# octopus_sch.net
KiCad netlist of a schematic drawn in Altium Designer
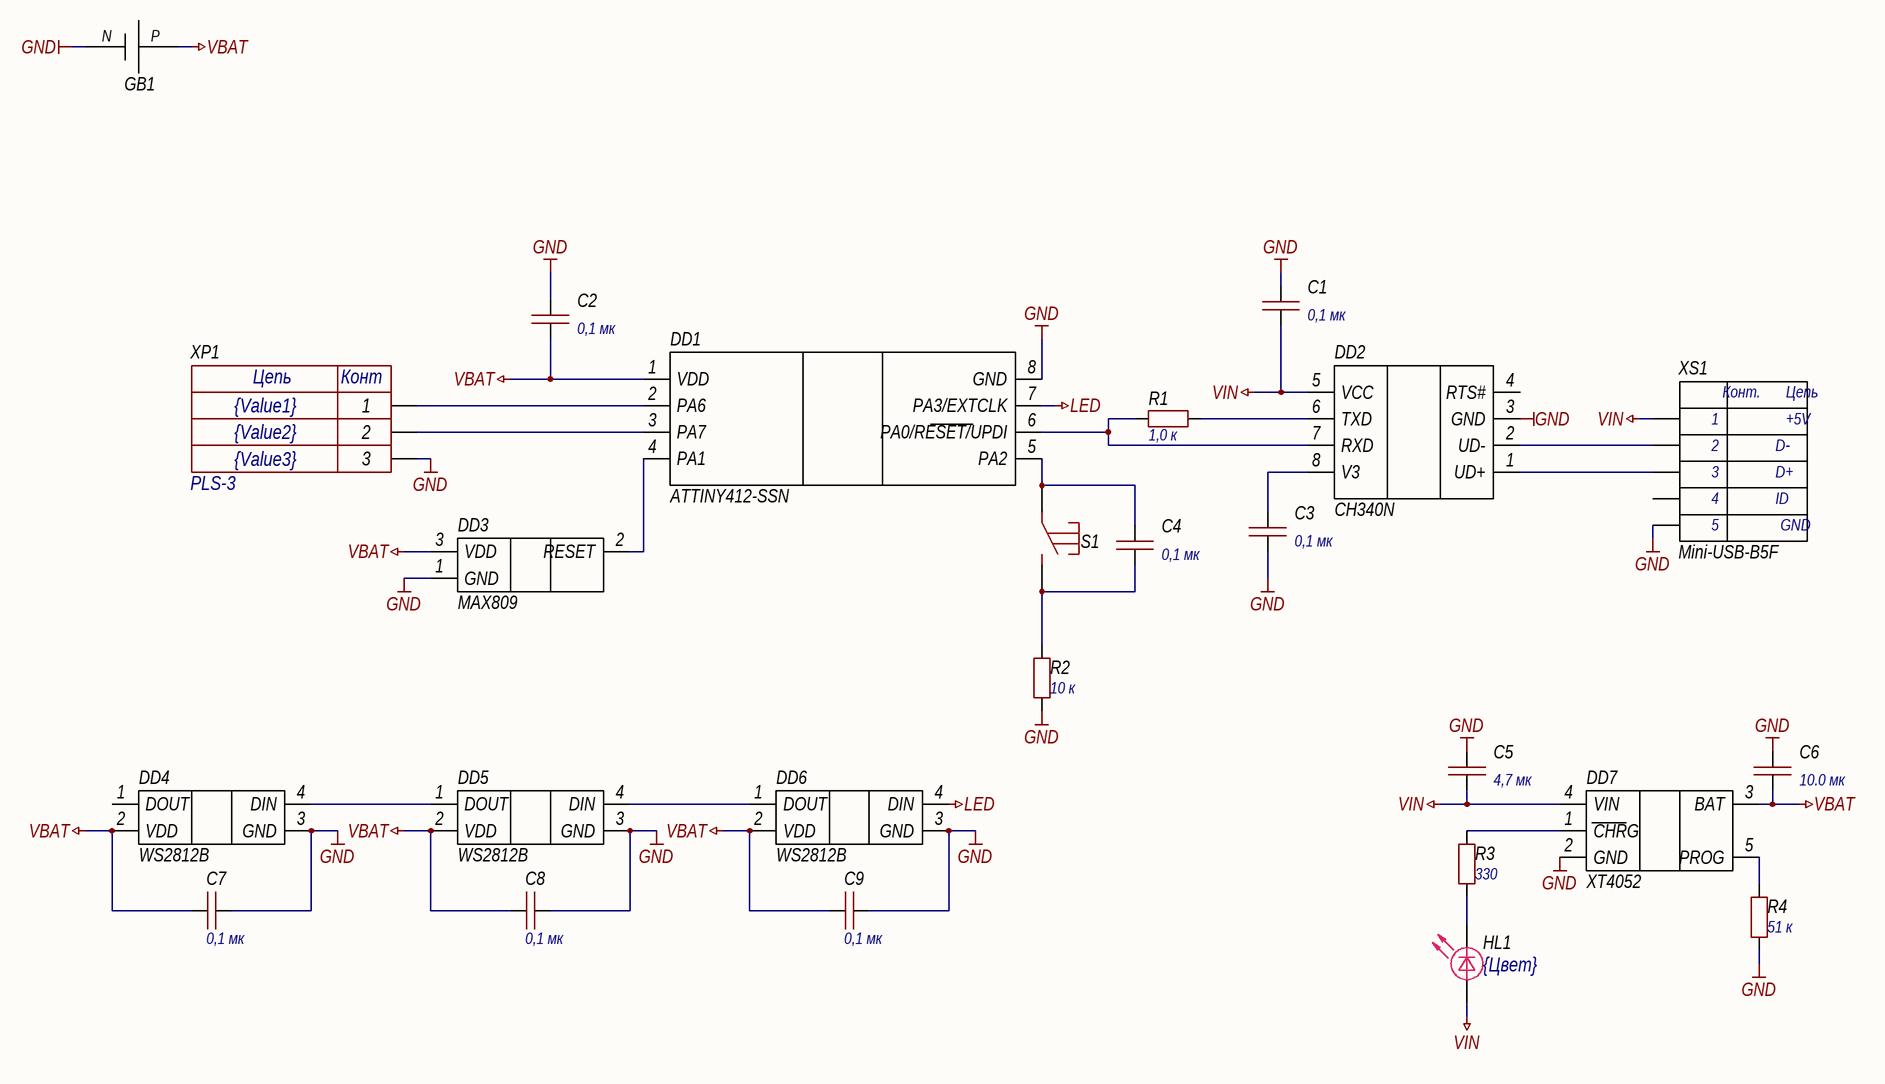
[diagram p0: octopus_sch.SchDoc]

(export (version "E")
  (design (tool "Eeschema 10.0.6"))
  (components
    (comp (ref "C1")
      (value "0,1 мк")
      (footprint "THT CAP")
      (description "Конденсатор")
      (fields (field (name "PART NUMBER") "Capacitor"))
      (libsource (lib "Hydrolib") (part "Capacitor"))
    )
    (comp (ref "C2")
      (value "0,1 мк")
      (footprint "THT CAP")
      (description "Конденсатор")
      (fields (field (name "PART NUMBER") "Capacitor"))
      (libsource (lib "Hydrolib") (part "Capacitor"))
    )
    (comp (ref "C3")
      (value "0,1 мк")
      (footprint "THT CAP")
      (description "Конденсатор")
      (fields (field (name "PART NUMBER") "Capacitor"))
      (libsource (lib "Hydrolib") (part "Capacitor"))
    )
    (comp (ref "C4")
      (value "0,1 мк")
      (footprint "THT CAP")
      (description "Конденсатор")
      (fields (field (name "PART NUMBER") "Capacitor"))
      (libsource (lib "Hydrolib") (part "Capacitor"))
    )
    (comp (ref "C5")
      (value "4,7 мк")
      (footprint "THT CAP")
      (description "Конденсатор")
      (fields (field (name "PART NUMBER") "Capacitor"))
      (libsource (lib "Hydrolib") (part "Capacitor"))
    )
    (comp (ref "C6")
      (value "10.0 мк")
      (footprint "THT CAP")
      (description "Конденсатор")
      (fields (field (name "PART NUMBER") "Capacitor"))
      (libsource (lib "Hydrolib") (part "Capacitor"))
    )
    (comp (ref "C7")
      (value "0,1 мк")
      (footprint "THT CAP")
      (description "Конденсатор")
      (fields (field (name "PART NUMBER") "Capacitor"))
      (libsource (lib "Hydrolib") (part "Capacitor"))
    )
    (comp (ref "C8")
      (value "0,1 мк")
      (footprint "THT CAP")
      (description "Конденсатор")
      (fields (field (name "PART NUMBER") "Capacitor"))
      (libsource (lib "Hydrolib") (part "Capacitor"))
    )
    (comp (ref "C9")
      (value "0,1 мк")
      (footprint "THT CAP")
      (description "Конденсатор")
      (fields (field (name "PART NUMBER") "Capacitor"))
      (libsource (lib "Hydrolib") (part "Capacitor"))
    )
    (comp (ref "DD1")
      (value "ATTINY412-SSN")
      (footprint "SOIC-8")
      (description "Микроконтроллер")
      (libsource (lib "Hydrolib") (part "ATTINY412-SSN"))
    )
    (comp (ref "DD2")
      (value "CH340N")
      (footprint "SOP8")
      (description "Преобразователь интерфейса USB в UART")
      (fields (field (name "АВТОР") "klegot"))
      (libsource (lib "Hydrolib") (part "CH340N"))
    )
    (comp (ref "DD3")
      (value "MAX809")
      (footprint "SOT23-3")
      (description "Формирователь импульса сброса (супервизор питания)")
      (fields (field (name "АВТОР") "klegot"))
      (libsource (lib "Hydrolib") (part "MAX809"))
    )
    (comp (ref "DD4")
      (value "WS2812B")
      (footprint "LED RGB horizontal")
      (description "Адресный светодиод")
      (fields (field (name "АВТОР") "klegot"))
      (libsource (lib "Hydrolib") (part "WS2812B"))
    )
    (comp (ref "DD5")
      (value "WS2812B")
      (footprint "LED_RGB_5MM")
      (description "Адресный светодиод")
      (fields (field (name "АВТОР") "klegot"))
      (libsource (lib "Hydrolib") (part "WS2812B"))
    )
    (comp (ref "DD6")
      (value "WS2812B")
      (footprint "LED_RGB_5MM")
      (description "Адресный светодиод")
      (fields (field (name "АВТОР") "klegot"))
      (libsource (lib "Hydrolib") (part "WS2812B"))
    )
    (comp (ref "DD7")
      (value "XT4052")
      (footprint "SOT23-5")
      (description "Контроллер заряда Li-Ion аккумуляторов, 4.2 В")
      (fields (field (name "АВТОР") "klegot"))
      (libsource (lib "Hydrolib") (part "XT4052"))
    )
    (comp (ref "GB1")
      (value "L-KLS5-CR2032-03")
      (footprint "L-KLS5-CR2032-03")
      (description "Держатель батареи CR2032")
      (fields (field (name "АВТОР") "klegot"))
      (libsource (lib "Hydrolib") (part "Battery"))
    )
    (comp (ref "HL1")
      (value "LED")
      (footprint "3mm_led_red")
      (description "Светодиод")
      (fields (field (name "COLOR") "{Цвет}"))
      (libsource (lib "Hydrolib") (part "LED"))
    )
    (comp (ref "R1")
      (value "1,0 к")
      (footprint "RES_THT_025W_1k")
      (description "Резистор номиналом 1,0 кОм 1%")
      (fields (field (name "PART NUMBER") "Resistor_1.0k_1_0603") (field (name "TOLERANCE") "1%"))
      (libsource (lib "") (part "Resistor_2"))
    )
    (comp (ref "R2")
      (value "10 к")
      (footprint "RES_THT_025W_10k")
      (description "Резистор номиналом 10 кОм 1%")
      (fields (field (name "PART NUMBER") "Resistor_10k_1_0603") (field (name "TOLERANCE") "1%"))
      (libsource (lib "") (part "Resistor_1"))
    )
    (comp (ref "R3")
      (value "330")
      (footprint "RES_THT_025W_1k")
      (description "Резистор номиналом 1,0 кОм 1%")
      (fields (field (name "PART NUMBER") "Resistor_1.0k_1_0603") (field (name "TOLERANCE") "1%"))
      (libsource (lib "Hydrolib") (part "Resistor"))
    )
    (comp (ref "R4")
      (value "51 к")
      (footprint "RES_THT_025W_100k")
      (description "Резистор номиналом 100 кОм 1%")
      (fields (field (name "PART NUMBER") "Resistor_100k_1_0603") (field (name "TOLERANCE") "1%"))
      (libsource (lib "Hydrolib") (part "Resistor"))
    )
    (comp (ref "S1")
      (value "KLS7-TS3601")
      (footprint "KLS7-TS3601")
      (description "Тактовая кнопка")
      (fields (field (name "АВТОР") "klegot"))
      (libsource (lib "Hydrolib") (part "Tact_button"))
    )
    (comp (ref "XP1")
      (value "PLS-3")
      (footprint "PLS3")
      (description "Гребенка 3 пина")
      (fields
        (field (name "VALUE3") "{Value3}")
        (field (name "VALUE2") "{Value2}")
        (field (name "VALUE1") "{Value1}")
        (field (name "АВТОР") "rreali")
      )
      (libsource (lib "Hydrolib") (part "Conn_3pin"))
    )
    (comp (ref "XS1")
      (value "Mini-USB-B5F")
      (footprint "KLS1-229-5FA")
      (description "Разъем mini USB, розетка угловая на плату")
      (fields (field (name "АВТОР") "klegot"))
      (libsource (lib "Hydrolib") (part "Mini-USB-B5F"))
    )
  )
  (nets
    (net (code "1") (name "GND") (class "Default")
      (node (ref "C1") (pin "1") (pinfunction "1_1") (pintype "passive"))
      (node (ref "C2") (pin "1") (pinfunction "1_1") (pintype "passive"))
      (node (ref "C3") (pin "1") (pinfunction "1_1") (pintype "passive"))
      (node (ref "C5") (pin "1") (pinfunction "1_1") (pintype "passive"))
      (node (ref "C6") (pin "1") (pinfunction "1_1") (pintype "passive"))
      (node (ref "C7") (pin "2") (pinfunction "2_2") (pintype "passive"))
      (node (ref "C8") (pin "2") (pinfunction "2_2") (pintype "passive"))
      (node (ref "C9") (pin "2") (pinfunction "2_2") (pintype "passive"))
      (node (ref "DD1") (pin "8") (pinfunction "GND_8") (pintype "passive"))
      (node (ref "DD2") (pin "3") (pinfunction "GND_3") (pintype "passive"))
      (node (ref "DD3") (pin "1") (pinfunction "GND_1") (pintype "passive"))
      (node (ref "DD4") (pin "3") (pinfunction "GND_3") (pintype "passive"))
      (node (ref "DD5") (pin "3") (pinfunction "GND_3") (pintype "passive"))
      (node (ref "DD6") (pin "3") (pinfunction "GND_3") (pintype "passive"))
      (node (ref "DD7") (pin "2") (pinfunction "GND_2") (pintype "passive"))
      (node (ref "GB1") (pin "N") (pinfunction "N_N") (pintype "passive"))
      (node (ref "R2") (pin "2") (pinfunction "2_2") (pintype "passive"))
      (node (ref "R4") (pin "1") (pinfunction "1_1") (pintype "passive"))
      (node (ref "XP1") (pin "3") (pinfunction "3_3") (pintype "passive"))
      (node (ref "XS1") (pin "5") (pinfunction "5_5") (pintype "passive"))
    )
    (net (code "2") (name "LED") (class "Default")
      (node (ref "DD1") (pin "7") (pinfunction "PA3/EXTCLK_7") (pintype "passive"))
      (node (ref "DD6") (pin "4") (pinfunction "DIN_4") (pintype "passive"))
    )
    (net (code "3") (name "Net-(C4-Pad1)") (class "Default")
      (node (ref "C4") (pin "1") (pinfunction "1_1") (pintype "passive"))
      (node (ref "R2") (pin "1") (pinfunction "1_1") (pintype "passive"))
      (node (ref "S1") (pin "2") (pinfunction "2_2") (pintype "passive"))
    )
    (net (code "4") (name "Net-(DD1-PA0{slash}RESET{slash}UPDI)") (class "Default")
      (node (ref "DD1") (pin "6") (pinfunction "PA0/RESET/UPDI_6") (pintype "passive"))
      (node (ref "DD2") (pin "7") (pinfunction "RXD_7") (pintype "passive"))
      (node (ref "R1") (pin "1") (pinfunction "1_1") (pintype "passive"))
    )
    (net (code "5") (name "Net-(DD1-PA1)") (class "Default")
      (node (ref "DD1") (pin "4") (pinfunction "PA1_4") (pintype "passive"))
      (node (ref "DD3") (pin "2") (pinfunction "RESET_2") (pintype "passive"))
    )
    (net (code "6") (name "Net-(DD1-PA2)") (class "Default")
      (node (ref "C4") (pin "2") (pinfunction "2_2") (pintype "passive"))
      (node (ref "DD1") (pin "5") (pinfunction "PA2_5") (pintype "passive"))
      (node (ref "S1") (pin "1") (pinfunction "1_1") (pintype "passive"))
    )
    (net (code "7") (name "Net-(DD1-PA6)") (class "Default")
      (node (ref "DD1") (pin "2") (pinfunction "PA6_2") (pintype "passive"))
      (node (ref "XP1") (pin "1") (pinfunction "1_1") (pintype "passive"))
    )
    (net (code "8") (name "Net-(DD1-PA7)") (class "Default")
      (node (ref "DD1") (pin "3") (pinfunction "PA7_3") (pintype "passive"))
      (node (ref "XP1") (pin "2") (pinfunction "2_2") (pintype "passive"))
    )
    (net (code "9") (name "Net-(DD2-TXD)") (class "Default")
      (node (ref "DD2") (pin "6") (pinfunction "TXD_6") (pintype "passive"))
      (node (ref "R1") (pin "2") (pinfunction "2_2") (pintype "passive"))
    )
    (net (code "10") (name "Net-(DD2-UD+)") (class "Default")
      (node (ref "DD2") (pin "1") (pinfunction "UD+_1") (pintype "passive"))
      (node (ref "XS1") (pin "3") (pinfunction "3_3") (pintype "passive"))
    )
    (net (code "11") (name "Net-(DD2-UD-)") (class "Default")
      (node (ref "DD2") (pin "2") (pinfunction "UD-_2") (pintype "passive"))
      (node (ref "XS1") (pin "2") (pinfunction "2_2") (pintype "passive"))
    )
    (net (code "12") (name "Net-(DD2-V3)") (class "Default")
      (node (ref "C3") (pin "2") (pinfunction "2_2") (pintype "passive"))
      (node (ref "DD2") (pin "8") (pinfunction "V3_8") (pintype "passive"))
    )
    (net (code "13") (name "Net-(DD4-DIN)") (class "Default")
      (node (ref "DD4") (pin "4") (pinfunction "DIN_4") (pintype "passive"))
      (node (ref "DD5") (pin "1") (pinfunction "DOUT_1") (pintype "passive"))
    )
    (net (code "14") (name "Net-(DD5-DIN)") (class "Default")
      (node (ref "DD5") (pin "4") (pinfunction "DIN_4") (pintype "passive"))
      (node (ref "DD6") (pin "1") (pinfunction "DOUT_1") (pintype "passive"))
    )
    (net (code "15") (name "Net-(DD7-CHRG)") (class "Default")
      (node (ref "DD7") (pin "1") (pinfunction "CHRG_1") (pintype "passive"))
      (node (ref "R3") (pin "2") (pinfunction "2_2") (pintype "passive"))
    )
    (net (code "16") (name "Net-(DD7-PROG)") (class "Default")
      (node (ref "DD7") (pin "5") (pinfunction "PROG_5") (pintype "passive"))
      (node (ref "R4") (pin "2") (pinfunction "2_2") (pintype "passive"))
    )
    (net (code "17") (name "Net-(HL1-Pad2)") (class "Default")
      (node (ref "HL1") (pin "2") (pinfunction "2_2") (pintype "passive"))
      (node (ref "R3") (pin "1") (pinfunction "1_1") (pintype "passive"))
    )
    (net (code "18") (name "VBAT") (class "Default")
      (node (ref "C2") (pin "2") (pinfunction "2_2") (pintype "passive"))
      (node (ref "C6") (pin "2") (pinfunction "2_2") (pintype "passive"))
      (node (ref "C7") (pin "1") (pinfunction "1_1") (pintype "passive"))
      (node (ref "C8") (pin "1") (pinfunction "1_1") (pintype "passive"))
      (node (ref "C9") (pin "1") (pinfunction "1_1") (pintype "passive"))
      (node (ref "DD1") (pin "1") (pinfunction "VDD_1") (pintype "passive"))
      (node (ref "DD3") (pin "3") (pinfunction "VDD_3") (pintype "passive"))
      (node (ref "DD4") (pin "2") (pinfunction "VDD_2") (pintype "passive"))
      (node (ref "DD5") (pin "2") (pinfunction "VDD_2") (pintype "passive"))
      (node (ref "DD6") (pin "2") (pinfunction "VDD_2") (pintype "passive"))
      (node (ref "DD7") (pin "3") (pinfunction "BAT_3") (pintype "passive"))
      (node (ref "GB1") (pin "P") (pinfunction "P_P") (pintype "passive"))
    )
    (net (code "19") (name "VIN") (class "Default")
      (node (ref "C1") (pin "2") (pinfunction "2_2") (pintype "passive"))
      (node (ref "C5") (pin "2") (pinfunction "2_2") (pintype "passive"))
      (node (ref "DD2") (pin "5") (pinfunction "VCC_5") (pintype "passive"))
      (node (ref "DD7") (pin "4") (pinfunction "VIN_4") (pintype "passive"))
      (node (ref "HL1") (pin "1") (pinfunction "1_1") (pintype "passive"))
      (node (ref "XS1") (pin "1") (pinfunction "1_1") (pintype "passive"))
    )
    (net (code "20") (name "unconnected-(DD2-RTS#-Pad4)") (class "Default")
      (node (ref "DD2") (pin "4") (pinfunction "RTS#_4") (pintype "passive"))
    )
    (net (code "21") (name "unconnected-(DD4-DOUT-Pad1)") (class "Default")
      (node (ref "DD4") (pin "1") (pinfunction "DOUT_1") (pintype "passive"))
    )
    (net (code "22") (name "unconnected-(XS1-Pad4)") (class "Default")
      (node (ref "XS1") (pin "4") (pinfunction "4_4") (pintype "passive"))
    )
  )
)
